# ProProject_Access_Control_Contactor_Swit.net
KiCad netlist of a schematic drawn in EasyEDA Pro
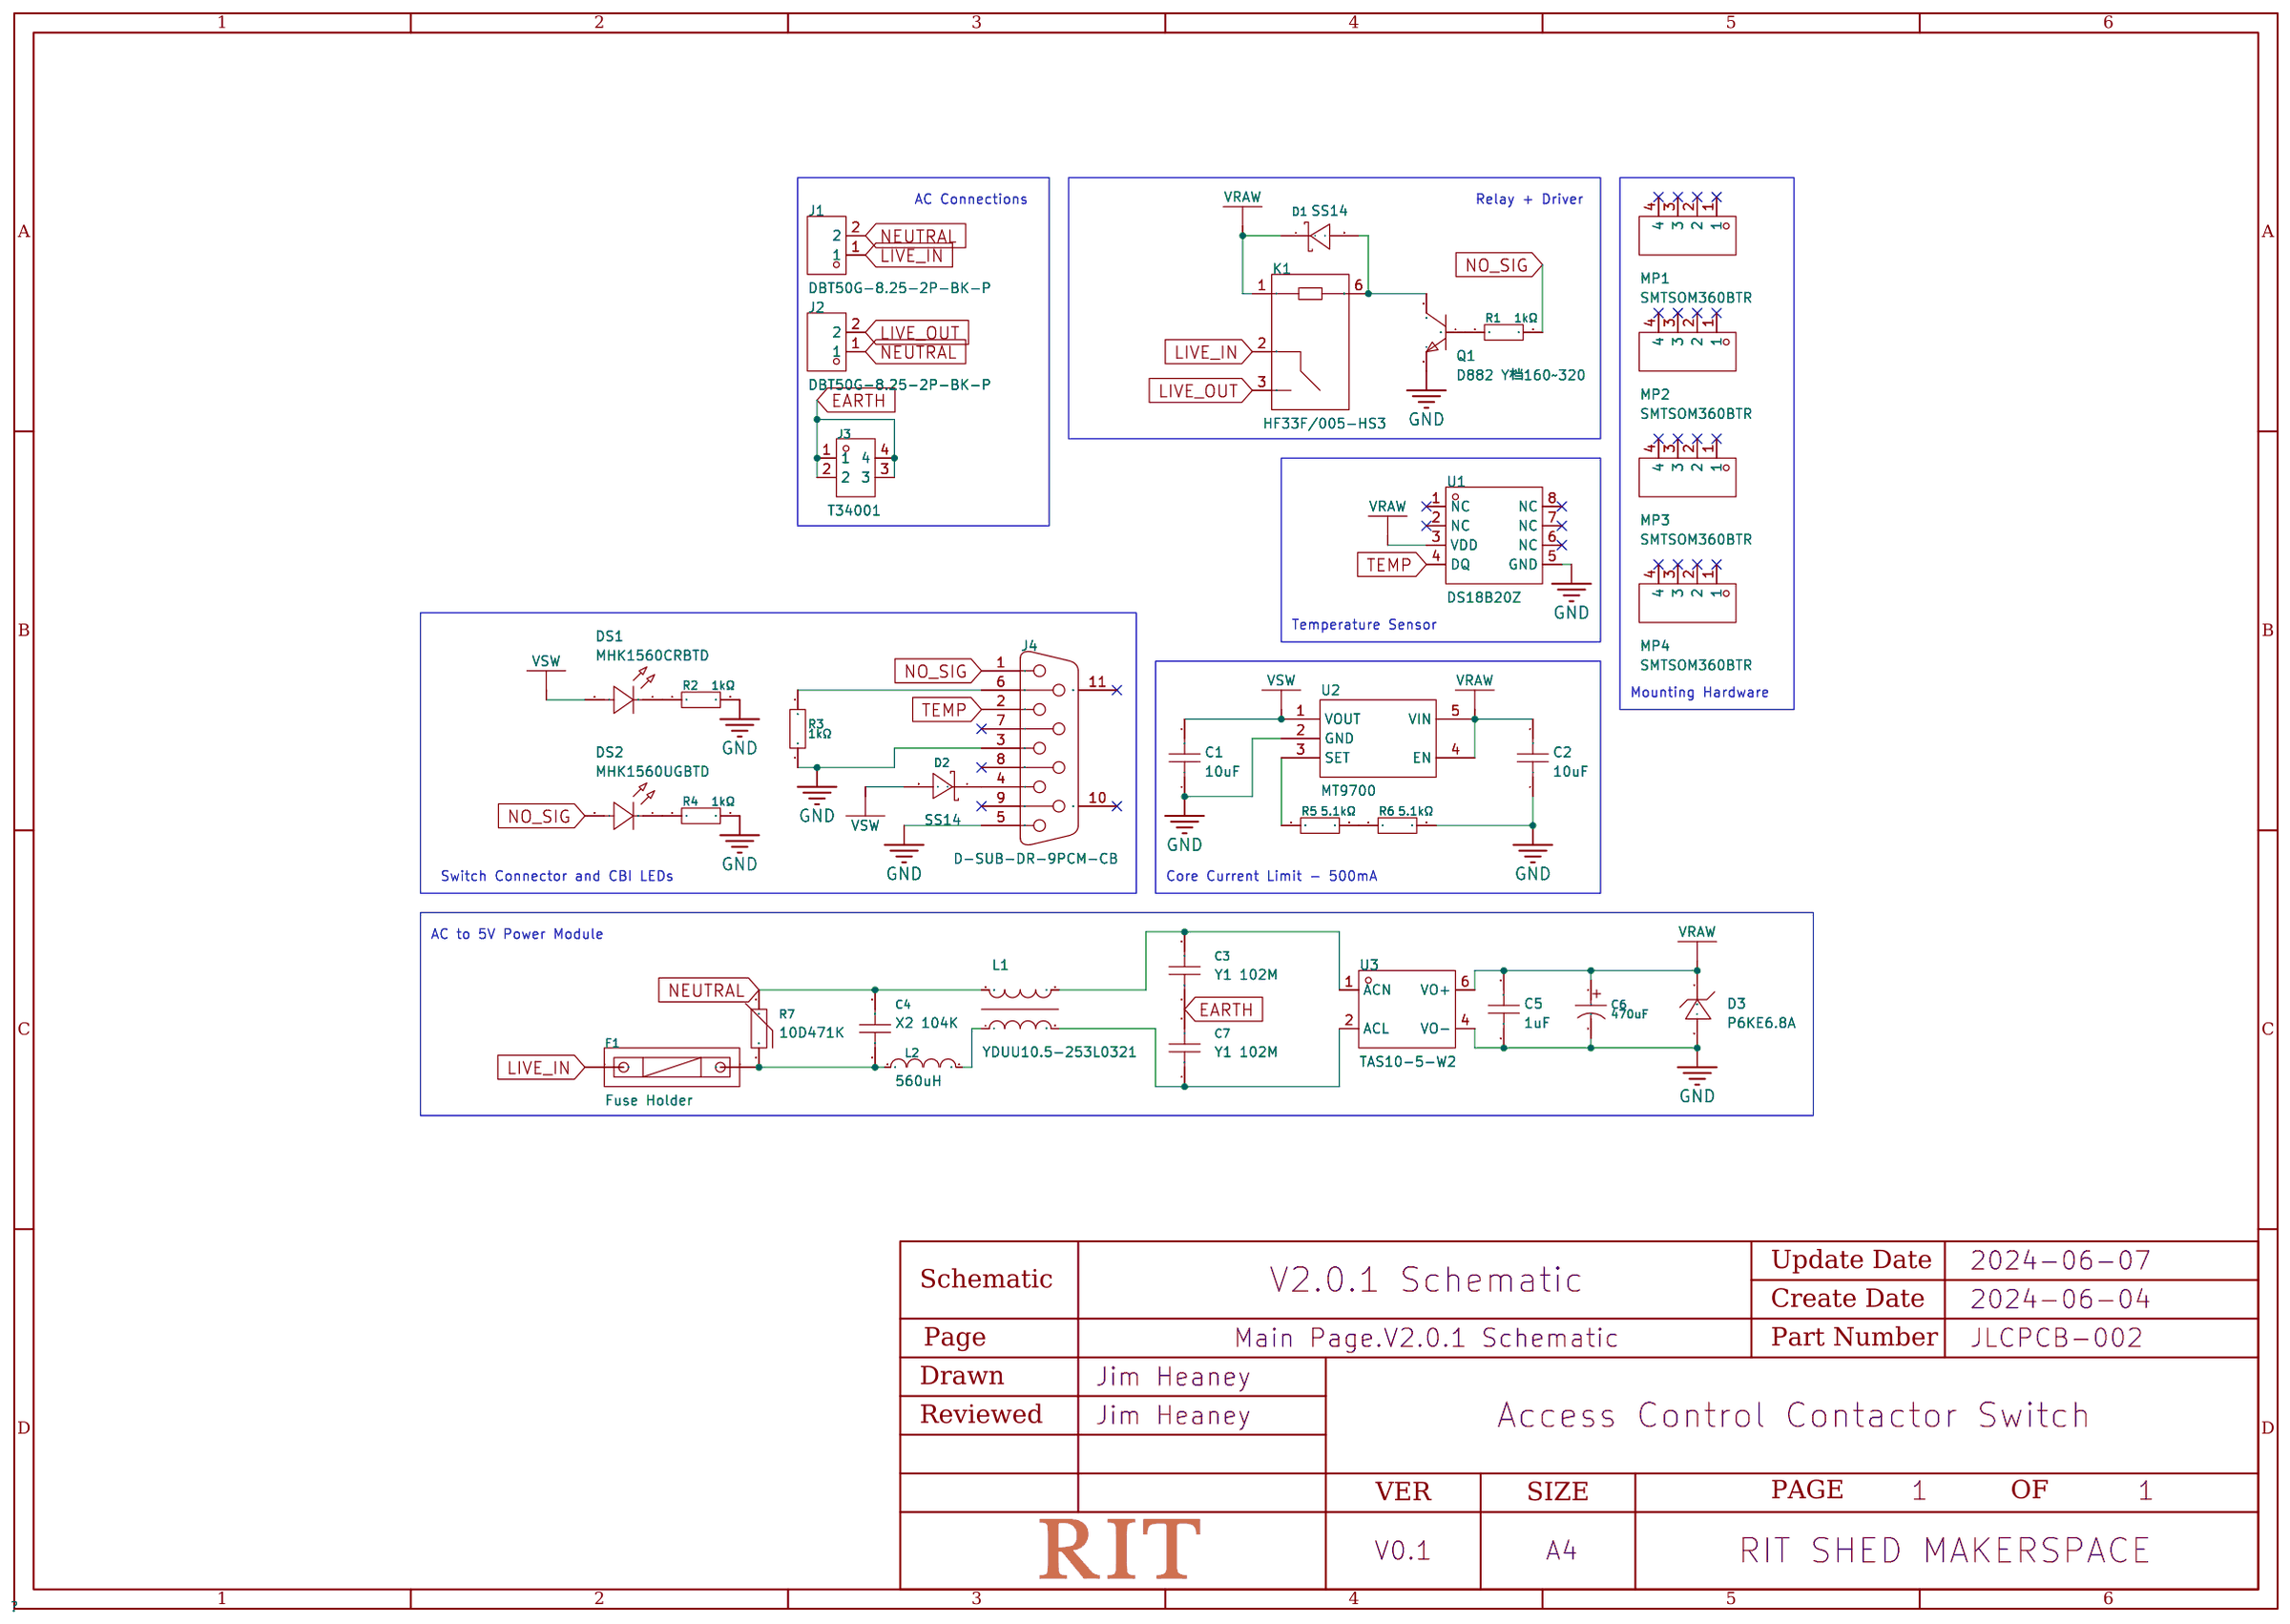
[diagram p0: schematic sheet]

(export (version "E")
  (design (tool "Eeschema 10.0.6"))
  (components
    (comp (ref "C1")
      (value "10uF")
      (footprint "easyedapro:C0603")
      (fields
        (field (name "Manufacturer Part") "CL10A106MA8NRNC")
        (field (name "Manufacturer") "SAMSUNG(三星)")
      )
      (libsource (lib "easyedapro") (part "CL10A106MA8NRNC"))
    )
    (comp (ref "C2")
      (value "10uF")
      (footprint "easyedapro:C0603")
      (fields
        (field (name "Manufacturer Part") "CL10A106MA8NRNC")
        (field (name "Manufacturer") "SAMSUNG(三星)")
      )
      (libsource (lib "easyedapro") (part "CL10A106MA8NRNC"))
    )
    (comp (ref "C3")
      (value "1nF")
      (footprint "easyedapro:CAP-TH_L8.5-W5.0-P10.00-D0.6")
      (fields
        (field (name "Manufacturer Part") "VY1102M31Y5UC63V0")
        (field (name "Manufacturer") "VISHAY(威世)")
      )
      (libsource (lib "easyedapro") (part "VY1102M31Y5UC63V0"))
    )
    (comp (ref "C4")
      (value "100nF")
      (footprint "easyedapro:CAP-TH_L10.0-W5.0-P7.50-D0.6")
      (fields (field (name "Manufacturer Part") "PX104K2C0702") (field (name "Manufacturer") "KYET(科雅)"))
      (libsource (lib "easyedapro") (part "PX104K2C0702"))
    )
    (comp (ref "C5")
      (value "1uF")
      (footprint "easyedapro:C1206")
      (fields
        (field (name "Manufacturer Part") "CL31B105KBHNNNE")
        (field (name "Manufacturer") "SAMSUNG(三星)")
      )
      (libsource (lib "easyedapro") (part "CL31B105KBHNNNE"))
    )
    (comp (ref "C6")
      (value "470uF")
      (footprint "easyedapro:CAP-TH_BD8.0-P3.50-D0.6-FD")
      (fields
        (field (name "Manufacturer Part") "NXA 16V470 8*11.5")
        (field (name "Manufacturer") "SAMYOUNG(韩国三莹)")
      )
      (libsource (lib "easyedapro") (part "NXA-16V470-8*11.5"))
    )
    (comp (ref "C7")
      (value "1nF")
      (footprint "easyedapro:CAP-TH_L8.5-W5.0-P10.00-D0.6")
      (fields
        (field (name "Manufacturer Part") "VY1102M31Y5UC63V0")
        (field (name "Manufacturer") "VISHAY(威世)")
      )
      (libsource (lib "easyedapro") (part "VY1102M31Y5UC63V0"))
    )
    (comp (ref "D1")
      (value "SS14")
      (footprint "easyedapro:SMA_L4.2-W2.6-LS5.3-RD")
      (fields (field (name "Manufacturer") "MDD"))
      (libsource (lib "easyedapro") (part "SS14"))
    )
    (comp (ref "D2")
      (value "SS14")
      (footprint "easyedapro:SMA_L4.2-W2.6-LS5.3-RD")
      (fields (field (name "Manufacturer") "MDD"))
      (libsource (lib "easyedapro") (part "SS14"))
    )
    (comp (ref "D3")
      (value "P6KE6.8A")
      (footprint "easyedapro:DO-15_BD3.1-L6.7-P10.70-D0.9-RD")
      (fields (field (name "Manufacturer") "Littelfuse(美国力特)"))
      (libsource (lib "easyedapro") (part "P6KE6.8A_C409413"))
    )
    (comp (ref "DS1")
      (value "MHK1560CRBTD")
      (footprint "easyedapro:LED-TH_MHK1560UGBTD")
      (fields (field (name "Manufacturer") "MEIHUA(美华)"))
      (libsource (lib "easyedapro") (part "MHK1560CGBTD"))
    )
    (comp (ref "DS2")
      (value "MHK1560UGBTD")
      (footprint "easyedapro:LED-TH_MHK1560UGBTD")
      (fields (field (name "Manufacturer") "MEIHUA(美华)"))
      (libsource (lib "easyedapro") (part "MHK1560UGBTD"))
    )
    (comp (ref "F1")
      (value "Fuse Holder")
      (footprint "easyedapro:FUSE-TH_L24.5-W9.8-P22.5")
      (description "Fuseholder Type:- Fuse Type:- Fuse Size:-")
      (fields (field (name "Manufacturer Part") "保险丝透明座") (field (name "Manufacturer") "xcfuse(旭程)"))
      (libsource (lib "easyedapro") (part "Fuse transparent seat"))
    )
    (comp (ref "J1")
      (value "DBT50G-8.25-2P-BK-P")
      (footprint "easyedapro:CONN-TH_DBT50G-8.25-2P")
      (fields (field (name "Manufacturer") "DORABO(地博电气)"))
      (libsource (lib "easyedapro") (part "DBT50G-8.25-2P"))
    )
    (comp (ref "J2")
      (value "DBT50G-8.25-2P-BK-P")
      (footprint "easyedapro:CONN-TH_DBT50G-8.25-2P")
      (fields (field (name "Manufacturer") "DORABO(地博电气)"))
      (libsource (lib "easyedapro") (part "DBT50G-8.25-2P"))
    )
    (comp (ref "J3")
      (value "T34001")
      (footprint "easyedapro:CONN-TH_T34001")
      (fields (field (name "Manufacturer") "XFCN(兴飞)"))
      (libsource (lib "easyedapro") (part "T34001"))
    )
    (comp (ref "J4")
      (value "D-SUB-DR-9PCM-CB")
      (footprint "easyedapro:DB9-TH_ID09S33E4GV00LF")
      (fields (field (name "Manufacturer") "XUNPU(讯普)"))
      (libsource (lib "easyedapro") (part "D-SUB-DR-9PCM-CB"))
    )
    (comp (ref "K1")
      (value "HF33F/005-HS3")
      (footprint "easyedapro:RELAYS-TH_HF33F-XX-HS1-XXX")
      (fields (field (name "Manufacturer") "HF(宏发)"))
      (libsource (lib "easyedapro") (part "HF33F/005-HS3"))
    )
    (comp (ref "L1")
      (value "YDUU10.5-253L0321")
      (footprint "easyedapro:IND-TH_4P-L19.0-W17.0")
      (description "Number of Lines:2 Withstanding Voltage:1.5kV@AC Inductance @ Frequency:25mH@1KHz")
      (fields (field (name "Manufacturer") "YJYCOIN(益嘉源)"))
      (libsource (lib "easyedapro") (part "YDUU10.5-253L0321"))
    )
    (comp (ref "L2")
      (value "560uH")
      (footprint "easyedapro:IND-TH_BD9.0-P5.00-D0.7")
      (description "Inductance: Tolerance:±10% Tolerance:±10% Rated Current: DC Resistance (DCR): Type:工字电感")
      (fields (field (name "Manufacturer Part") "PK0810-561KB") (field (name "Manufacturer") "SXN(顺翔诺)"))
      (libsource (lib "easyedapro") (part "PK0810-561KB"))
    )
    (comp (ref "MP1")
      (value "SMTSOM360BTR")
      (footprint "easyedapro:SMD_BD5.6-D4.1")
      (fields (field (name "Manufacturer") "YIYUAN(怡远)"))
      (libsource (lib "easyedapro") (part "SMTSOM360BTR"))
    )
    (comp (ref "MP2")
      (value "SMTSOM360BTR")
      (footprint "easyedapro:SMD_BD5.6-D4.1")
      (fields (field (name "Manufacturer") "YIYUAN(怡远)"))
      (libsource (lib "easyedapro") (part "SMTSOM360BTR"))
    )
    (comp (ref "MP3")
      (value "SMTSOM360BTR")
      (footprint "easyedapro:SMD_BD5.6-D4.1")
      (fields (field (name "Manufacturer") "YIYUAN(怡远)"))
      (libsource (lib "easyedapro") (part "SMTSOM360BTR"))
    )
    (comp (ref "MP4")
      (value "SMTSOM360BTR")
      (footprint "easyedapro:SMD_BD5.6-D4.1")
      (fields (field (name "Manufacturer") "YIYUAN(怡远)"))
      (libsource (lib "easyedapro") (part "SMTSOM360BTR"))
    )
    (comp (ref "Q1")
      (value "D882 Y档160~320")
      (footprint "easyedapro:SOT-89-3_L4.5-W2.5-P1.50-LS4.2-BR")
      (fields (field (name "Manufacturer") "CJ(江苏长电/长晶)"))
      (libsource (lib "easyedapro") (part "D882_C9634"))
    )
    (comp (ref "R1")
      (value "1kΩ")
      (footprint "easyedapro:R0603")
      (fields
        (field (name "Manufacturer Part") "0603WAF1001T5E")
        (field (name "Manufacturer") "UNI-ROYAL(厚声)")
      )
      (libsource (lib "easyedapro") (part "0603WAF1001T5E"))
    )
    (comp (ref "R2")
      (value "1kΩ")
      (footprint "easyedapro:R0603")
      (fields
        (field (name "Manufacturer Part") "0603WAF1001T5E")
        (field (name "Manufacturer") "UNI-ROYAL(厚声)")
      )
      (libsource (lib "easyedapro") (part "0603WAF1001T5E"))
    )
    (comp (ref "R3")
      (value "1kΩ")
      (footprint "easyedapro:R0603")
      (fields
        (field (name "Manufacturer Part") "0603WAF1001T5E")
        (field (name "Manufacturer") "UNI-ROYAL(厚声)")
      )
      (libsource (lib "easyedapro") (part "0603WAF1001T5E"))
    )
    (comp (ref "R4")
      (value "1kΩ")
      (footprint "easyedapro:R0603")
      (fields
        (field (name "Manufacturer Part") "0603WAF1001T5E")
        (field (name "Manufacturer") "UNI-ROYAL(厚声)")
      )
      (libsource (lib "easyedapro") (part "0603WAF1001T5E"))
    )
    (comp (ref "R5")
      (value "5.1kΩ")
      (footprint "easyedapro:R0603")
      (fields
        (field (name "Manufacturer Part") "0603WAF5101T5E")
        (field (name "Manufacturer") "UNI-ROYAL(厚声)")
      )
      (libsource (lib "easyedapro") (part "0603WAF5101T5E"))
    )
    (comp (ref "R6")
      (value "5.1kΩ")
      (footprint "easyedapro:R0603")
      (fields
        (field (name "Manufacturer Part") "0603WAF5101T5E")
        (field (name "Manufacturer") "UNI-ROYAL(厚声)")
      )
      (libsource (lib "easyedapro") (part "0603WAF5101T5E"))
    )
    (comp (ref "R7")
      (value "10D471K")
      (footprint "easyedapro:RES-TH_L12.5-W6.7-P7.50-D1.2")
      (fields (field (name "Manufacturer") "RUILON(瑞隆源)"))
      (libsource (lib "easyedapro") (part "10D471K-C8760"))
    )
    (comp (ref "U1")
      (value "DS18B20Z")
      (footprint "easyedapro:SOP-8_L4.9-W3.9-P1.27-LS6.0-BL")
      (description "Resolution:±0.4°C Resolution:±0.4°C Supply Voltage:2.5V~5.5V Supply Voltage:2.5V~5.5V")
      (fields (field (name "Manufacturer") "UMW(友台半导体)"))
      (libsource (lib "easyedapro") (part "DS18B20Z"))
    )
    (comp (ref "U2")
      (value "MT9700")
      (footprint "easyedapro:SOT-23-5_L3.0-W1.7-P0.95-LS2.8-BR")
      (fields (field (name "Manufacturer") "西安航天民芯"))
      (libsource (lib "easyedapro") (part "MT9700"))
    )
    (comp (ref "U3")
      (value "TAS10-5-W2")
      (footprint "easyedapro:PWRM-TH_TAS10-XX-W2")
      (fields (field (name "Manufacturer") "TDPOWER(腾达电源)"))
      (libsource (lib "easyedapro") (part "TAS10-5-W2"))
    )
  )
  (nets
    (net (code "1") (name "EARTH") (class "Default")
      (node (ref "C3") (pin "1") (pinfunction "1_1") (pintype "input"))
      (node (ref "C7") (pin "2") (pinfunction "2_2") (pintype "input"))
      (node (ref "J3") (pin "1") (pinfunction "1_1") (pintype "input"))
      (node (ref "J3") (pin "2") (pinfunction "2_2") (pintype "input"))
      (node (ref "J3") (pin "3") (pinfunction "3_3") (pintype "input"))
      (node (ref "J3") (pin "4") (pinfunction "4_4") (pintype "input"))
    )
    (net (code "2") (name "GND") (class "Default")
      (node (ref "C1") (pin "1") (pinfunction "1_1") (pintype "input"))
      (node (ref "C2") (pin "1") (pinfunction "1_1") (pintype "input"))
      (node (ref "C5") (pin "1") (pinfunction "1_1") (pintype "unspecified"))
      (node (ref "C6") (pin "2") (pinfunction "2_2") (pintype "input"))
      (node (ref "D3") (pin "2") (pinfunction "A_2") (pintype "input"))
      (node (ref "J4") (pin "3") (pinfunction "3_3") (pintype "input"))
      (node (ref "J4") (pin "5") (pinfunction "5_5") (pintype "input"))
      (node (ref "Q1") (pin "3") (pinfunction "E_3") (pintype "input"))
      (node (ref "R2") (pin "2") (pinfunction "2_2") (pintype "input"))
      (node (ref "R3") (pin "1") (pinfunction "1_1") (pintype "input"))
      (node (ref "R4") (pin "2") (pinfunction "2_2") (pintype "input"))
      (node (ref "R6") (pin "2") (pinfunction "2_2") (pintype "input"))
      (node (ref "U1") (pin "5") (pinfunction "GND_5") (pintype "unspecified"))
      (node (ref "U2") (pin "2") (pinfunction "GND_2") (pintype "input"))
      (node (ref "U3") (pin "4") (pinfunction "VO-_4") (pintype "unspecified"))
    )
    (net (code "3") (name "LIVE_IN") (class "Default")
      (node (ref "F1") (pin "1") (pinfunction "1_1") (pintype "input"))
      (node (ref "J1") (pin "1") (pinfunction "1_1") (pintype "unspecified"))
      (node (ref "K1") (pin "2") (pinfunction "2_2") (pintype "input"))
    )
    (net (code "4") (name "LIVE_OUT") (class "Default")
      (node (ref "J2") (pin "2") (pinfunction "2_2") (pintype "unspecified"))
      (node (ref "K1") (pin "3") (pinfunction "3_3") (pintype "input"))
    )
    (net (code "5") (name "NEUTRAL") (class "Default")
      (node (ref "C4") (pin "2") (pinfunction "2_2") (pintype "input"))
      (node (ref "J1") (pin "2") (pinfunction "2_2") (pintype "unspecified"))
      (node (ref "J2") (pin "1") (pinfunction "1_1") (pintype "unspecified"))
      (node (ref "L1") (pin "3") (pinfunction "3_3") (pintype "unspecified"))
      (node (ref "R7") (pin "2") (pinfunction "2_2") (pintype "input"))
    )
    (net (code "6") (name "NO_SIG") (class "Default")
      (node (ref "DS2") (pin "2") (pinfunction "A_2") (pintype "unspecified"))
      (node (ref "J4") (pin "1") (pinfunction "1_1") (pintype "input"))
      (node (ref "R1") (pin "2") (pinfunction "2_2") (pintype "input"))
    )
    (net (code "7") (name "Net-(C4-Pad1)") (class "Default")
      (node (ref "C4") (pin "1") (pinfunction "1_1") (pintype "input"))
      (node (ref "F1") (pin "2") (pinfunction "2_2") (pintype "input"))
      (node (ref "L2") (pin "1") (pinfunction "1_1") (pintype "input"))
      (node (ref "R7") (pin "1") (pinfunction "1_1") (pintype "input"))
    )
    (net (code "8") (name "Net-(D1-A)") (class "Default")
      (node (ref "D1") (pin "2") (pinfunction "A_2") (pintype "input"))
      (node (ref "K1") (pin "6") (pinfunction "6_6") (pintype "input"))
      (node (ref "Q1") (pin "2") (pinfunction "C_2") (pintype "input"))
    )
    (net (code "9") (name "Net-(D2-K)") (class "Default")
      (node (ref "D2") (pin "1") (pinfunction "K_1") (pintype "input"))
      (node (ref "J4") (pin "4") (pinfunction "4_4") (pintype "input"))
    )
    (net (code "10") (name "Net-(DS1-K)") (class "Default")
      (node (ref "DS1") (pin "1") (pinfunction "K_1") (pintype "unspecified"))
      (node (ref "R2") (pin "1") (pinfunction "1_1") (pintype "input"))
    )
    (net (code "11") (name "Net-(DS2-K)") (class "Default")
      (node (ref "DS2") (pin "1") (pinfunction "K_1") (pintype "unspecified"))
      (node (ref "R4") (pin "1") (pinfunction "1_1") (pintype "input"))
    )
    (net (code "12") (name "Net-(J4-Pad6)") (class "Default")
      (node (ref "J4") (pin "6") (pinfunction "6_6") (pintype "input"))
      (node (ref "R3") (pin "2") (pinfunction "2_2") (pintype "input"))
    )
    (net (code "13") (name "Net-(L1-Pad4)") (class "Default")
      (node (ref "L1") (pin "4") (pinfunction "4_4") (pintype "unspecified"))
      (node (ref "L2") (pin "2") (pinfunction "2_2") (pintype "input"))
    )
    (net (code "14") (name "Net-(Q1-B)") (class "Default")
      (node (ref "Q1") (pin "1") (pinfunction "B_1") (pintype "input"))
      (node (ref "R1") (pin "1") (pinfunction "1_1") (pintype "input"))
    )
    (net (code "15") (name "Net-(R5-Pad2)") (class "Default")
      (node (ref "R5") (pin "2") (pinfunction "2_2") (pintype "input"))
      (node (ref "R6") (pin "1") (pinfunction "1_1") (pintype "input"))
    )
    (net (code "16") (name "Net-(U2-SET)") (class "Default")
      (node (ref "R5") (pin "1") (pinfunction "1_1") (pintype "input"))
      (node (ref "U2") (pin "3") (pinfunction "SET_3") (pintype "input"))
    )
    (net (code "17") (name "Net-(U3-ACL)") (class "Default")
      (node (ref "C7") (pin "1") (pinfunction "1_1") (pintype "input"))
      (node (ref "L1") (pin "2") (pinfunction "2_2") (pintype "unspecified"))
      (node (ref "U3") (pin "2") (pinfunction "ACL_2") (pintype "unspecified"))
    )
    (net (code "18") (name "Net-(U3-ACN)") (class "Default")
      (node (ref "C3") (pin "2") (pinfunction "2_2") (pintype "input"))
      (node (ref "L1") (pin "1") (pinfunction "1_1") (pintype "unspecified"))
      (node (ref "U3") (pin "1") (pinfunction "ACN_1") (pintype "unspecified"))
    )
    (net (code "19") (name "TEMP") (class "Default")
      (node (ref "J4") (pin "2") (pinfunction "2_2") (pintype "input"))
      (node (ref "U1") (pin "4") (pinfunction "DQ_4") (pintype "unspecified"))
    )
    (net (code "20") (name "VRAW") (class "Default")
      (node (ref "C2") (pin "2") (pinfunction "2_2") (pintype "input"))
      (node (ref "C5") (pin "2") (pinfunction "2_2") (pintype "unspecified"))
      (node (ref "C6") (pin "1") (pinfunction "1_1") (pintype "input"))
      (node (ref "D1") (pin "1") (pinfunction "K_1") (pintype "input"))
      (node (ref "D3") (pin "1") (pinfunction "C_1") (pintype "input"))
      (node (ref "K1") (pin "1") (pinfunction "1_1") (pintype "input"))
      (node (ref "U1") (pin "3") (pinfunction "VDD_3") (pintype "unspecified"))
      (node (ref "U2") (pin "4") (pinfunction "EN_4") (pintype "input"))
      (node (ref "U2") (pin "5") (pinfunction "VIN_5") (pintype "input"))
      (node (ref "U3") (pin "6") (pinfunction "VO+_6") (pintype "unspecified"))
    )
    (net (code "21") (name "VSW") (class "Default")
      (node (ref "C1") (pin "2") (pinfunction "2_2") (pintype "input"))
      (node (ref "D2") (pin "2") (pinfunction "A_2") (pintype "input"))
      (node (ref "DS1") (pin "2") (pinfunction "A_2") (pintype "unspecified"))
      (node (ref "U2") (pin "1") (pinfunction "VOUT_1") (pintype "input"))
    )
    (net (code "22") (name "unconnected-(J4-MH1-Pad10)") (class "Default")
      (node (ref "J4") (pin "10") (pinfunction "MH1_10") (pintype "input+no_connect"))
    )
    (net (code "23") (name "unconnected-(J4-MH2-Pad11)") (class "Default")
      (node (ref "J4") (pin "11") (pinfunction "MH2_11") (pintype "input+no_connect"))
    )
    (net (code "24") (name "unconnected-(J4-Pad7)") (class "Default")
      (node (ref "J4") (pin "7") (pinfunction "7_7") (pintype "input+no_connect"))
    )
    (net (code "25") (name "unconnected-(J4-Pad8)") (class "Default")
      (node (ref "J4") (pin "8") (pinfunction "8_8") (pintype "input+no_connect"))
    )
    (net (code "26") (name "unconnected-(J4-Pad9)") (class "Default")
      (node (ref "J4") (pin "9") (pinfunction "9_9") (pintype "input+no_connect"))
    )
    (net (code "27") (name "unconnected-(MP1-Pad1)") (class "Default")
      (node (ref "MP1") (pin "1") (pinfunction "1_1") (pintype "unspecified+no_connect"))
    )
    (net (code "28") (name "unconnected-(MP1-Pad2)") (class "Default")
      (node (ref "MP1") (pin "2") (pinfunction "2_2") (pintype "unspecified+no_connect"))
    )
    (net (code "29") (name "unconnected-(MP1-Pad3)") (class "Default")
      (node (ref "MP1") (pin "3") (pinfunction "3_3") (pintype "unspecified+no_connect"))
    )
    (net (code "30") (name "unconnected-(MP1-Pad4)") (class "Default")
      (node (ref "MP1") (pin "4") (pinfunction "4_4") (pintype "unspecified+no_connect"))
    )
    (net (code "31") (name "unconnected-(MP2-Pad1)") (class "Default")
      (node (ref "MP2") (pin "1") (pinfunction "1_1") (pintype "unspecified+no_connect"))
    )
    (net (code "32") (name "unconnected-(MP2-Pad2)") (class "Default")
      (node (ref "MP2") (pin "2") (pinfunction "2_2") (pintype "unspecified+no_connect"))
    )
    (net (code "33") (name "unconnected-(MP2-Pad3)") (class "Default")
      (node (ref "MP2") (pin "3") (pinfunction "3_3") (pintype "unspecified+no_connect"))
    )
    (net (code "34") (name "unconnected-(MP2-Pad4)") (class "Default")
      (node (ref "MP2") (pin "4") (pinfunction "4_4") (pintype "unspecified+no_connect"))
    )
    (net (code "35") (name "unconnected-(MP3-Pad1)") (class "Default")
      (node (ref "MP3") (pin "1") (pinfunction "1_1") (pintype "unspecified+no_connect"))
    )
    (net (code "36") (name "unconnected-(MP3-Pad2)") (class "Default")
      (node (ref "MP3") (pin "2") (pinfunction "2_2") (pintype "unspecified+no_connect"))
    )
    (net (code "37") (name "unconnected-(MP3-Pad3)") (class "Default")
      (node (ref "MP3") (pin "3") (pinfunction "3_3") (pintype "unspecified+no_connect"))
    )
    (net (code "38") (name "unconnected-(MP3-Pad4)") (class "Default")
      (node (ref "MP3") (pin "4") (pinfunction "4_4") (pintype "unspecified+no_connect"))
    )
    (net (code "39") (name "unconnected-(MP4-Pad1)") (class "Default")
      (node (ref "MP4") (pin "1") (pinfunction "1_1") (pintype "unspecified+no_connect"))
    )
    (net (code "40") (name "unconnected-(MP4-Pad2)") (class "Default")
      (node (ref "MP4") (pin "2") (pinfunction "2_2") (pintype "unspecified+no_connect"))
    )
    (net (code "41") (name "unconnected-(MP4-Pad3)") (class "Default")
      (node (ref "MP4") (pin "3") (pinfunction "3_3") (pintype "unspecified+no_connect"))
    )
    (net (code "42") (name "unconnected-(MP4-Pad4)") (class "Default")
      (node (ref "MP4") (pin "4") (pinfunction "4_4") (pintype "unspecified+no_connect"))
    )
    (net (code "43") (name "unconnected-(U1-NC-Pad1)") (class "Default")
      (node (ref "U1") (pin "1") (pinfunction "NC_1") (pintype "unspecified+no_connect"))
    )
    (net (code "44") (name "unconnected-(U1-NC-Pad2)") (class "Default")
      (node (ref "U1") (pin "2") (pinfunction "NC_2") (pintype "unspecified+no_connect"))
    )
    (net (code "45") (name "unconnected-(U1-NC-Pad6)") (class "Default")
      (node (ref "U1") (pin "6") (pinfunction "NC_6") (pintype "unspecified+no_connect"))
    )
    (net (code "46") (name "unconnected-(U1-NC-Pad7)") (class "Default")
      (node (ref "U1") (pin "7") (pinfunction "NC_7") (pintype "unspecified+no_connect"))
    )
    (net (code "47") (name "unconnected-(U1-NC-Pad8)") (class "Default")
      (node (ref "U1") (pin "8") (pinfunction "NC_8") (pintype "unspecified+no_connect"))
    )
  )
)
